# main-unit-psu.net
KiCad netlist of a schematic drawn in EAGLE
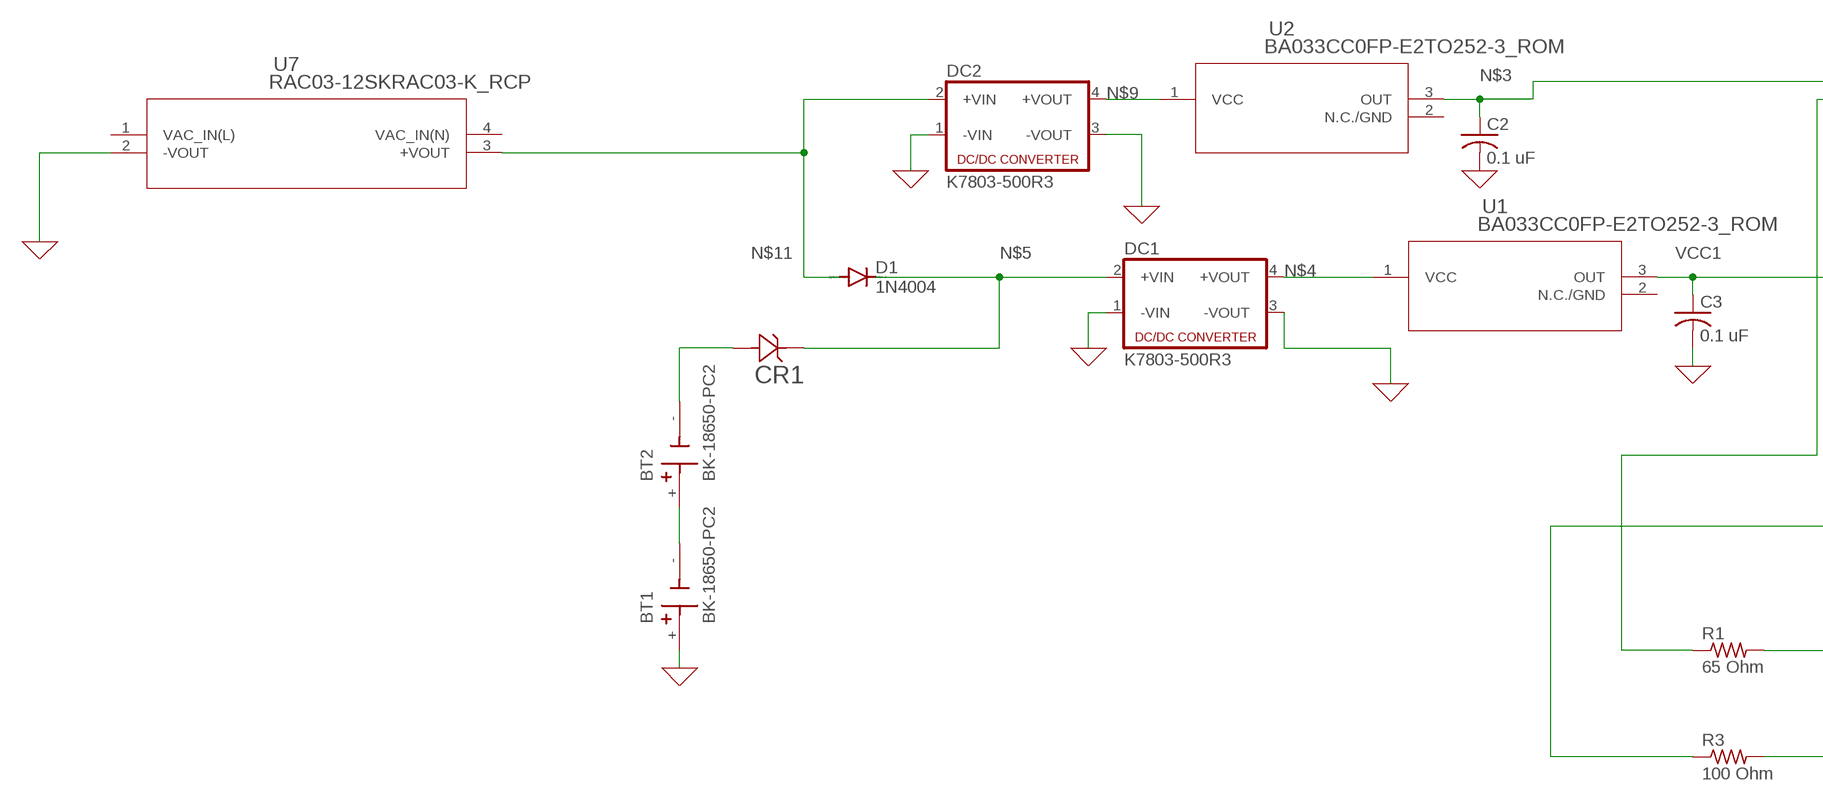
[diagram p0: schematic, sheet 1, part 1 of 2]
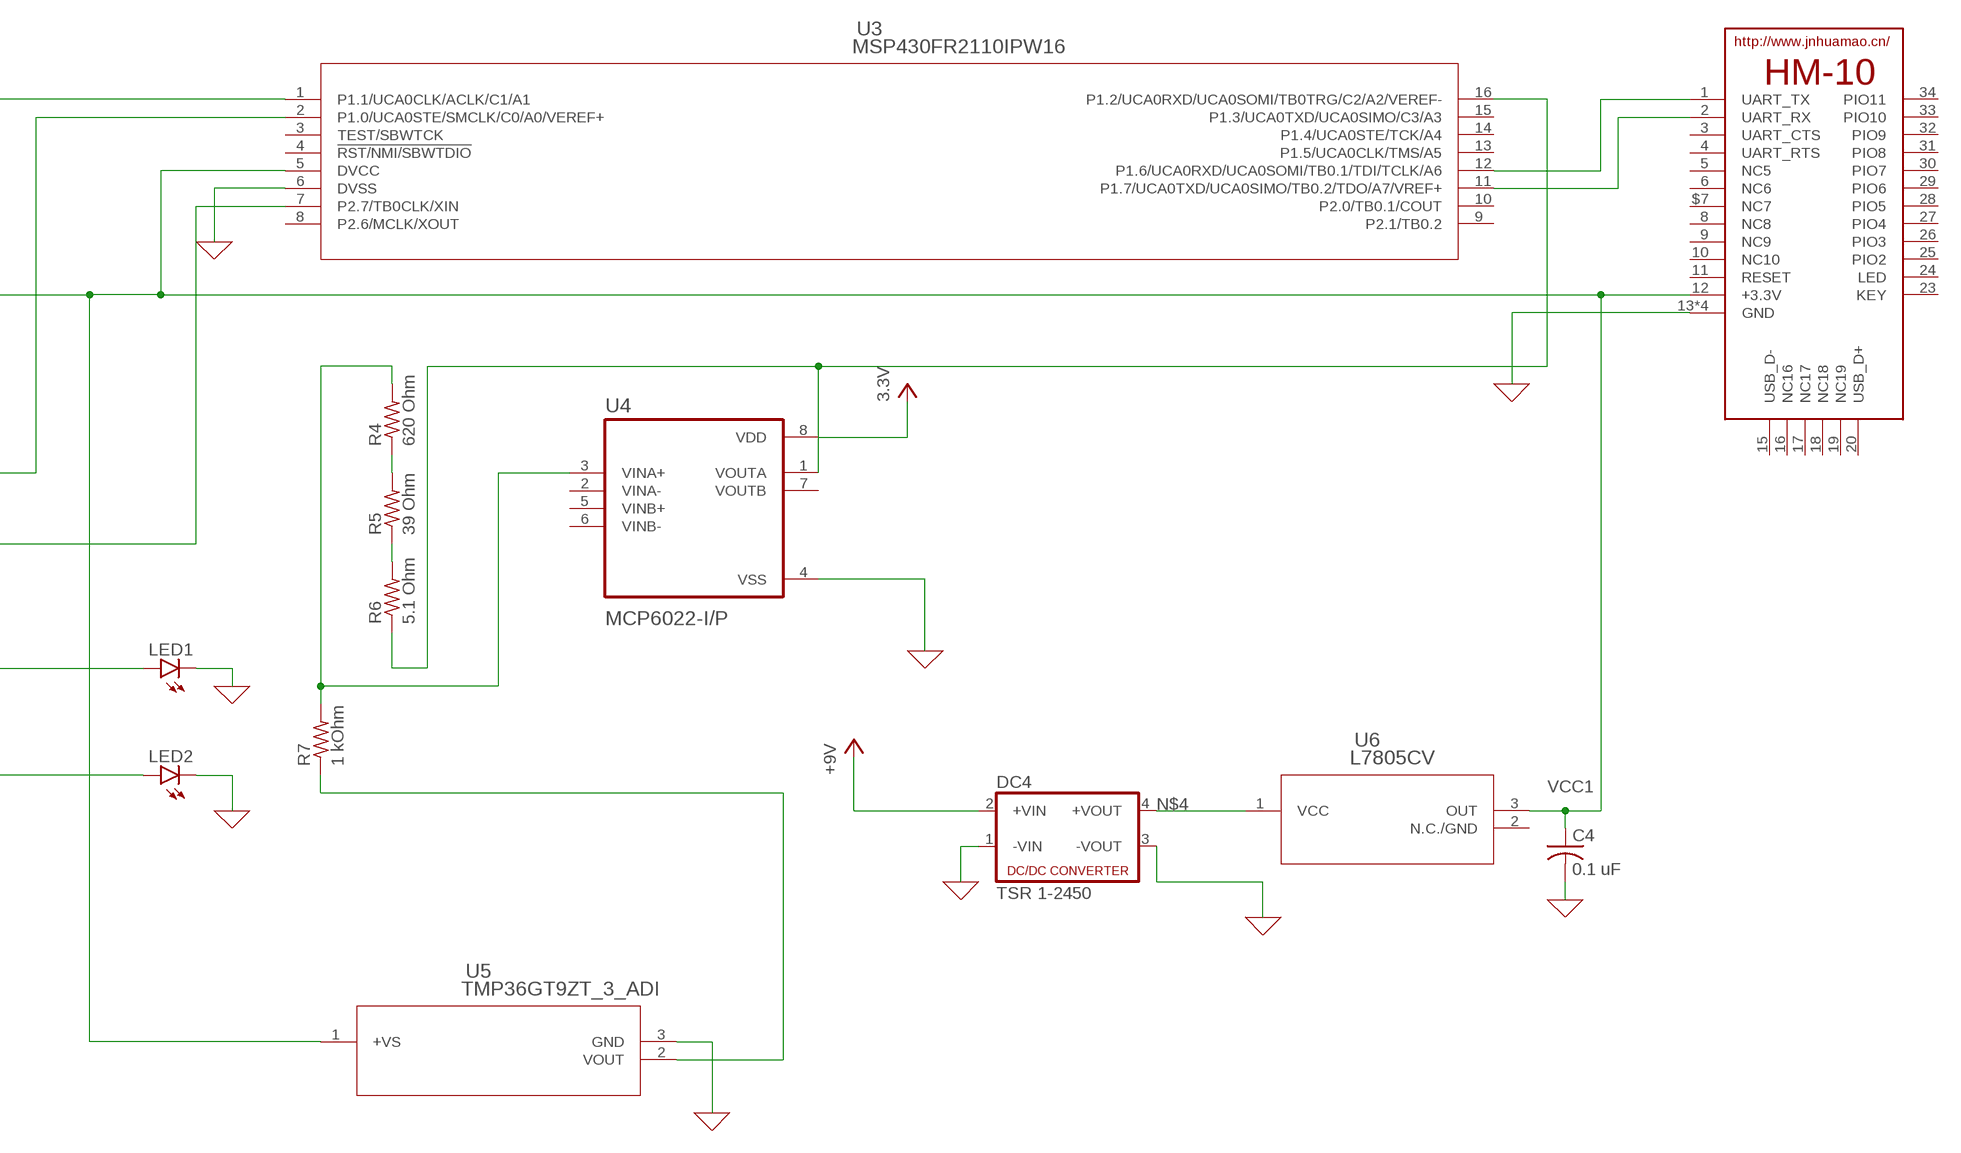
[diagram p1: schematic, sheet 1, part 2 of 2]

(export (version "E")
  (design (tool "Eeschema 10.0.6"))
  (components
    (comp (ref "BT1")
      (value "BK-18650-PC2")
      (footprint "eagle-import:BAT_BK-18650-PC2")
      (fields (field (name "MF") "MPD (Memory Protection Devices)"))
      (libsource (lib "eagle-import") (part "BK-18650-PC2"))
    )
    (comp (ref "BT2")
      (value "BK-18650-PC2")
      (footprint "eagle-import:BAT_BK-18650-PC2")
      (fields (field (name "MF") "MPD (Memory Protection Devices)"))
      (libsource (lib "eagle-import") (part "BK-18650-PC2"))
    )
    (comp (ref "C2")
      (value "0.1 uF")
      (footprint "eagle-import:C050-024X044")
      (libsource (lib "eagle-import") (part "C-US050-024X044"))
    )
    (comp (ref "C3")
      (value "0.1 uF")
      (footprint "eagle-import:C050-024X044")
      (libsource (lib "eagle-import") (part "C-US050-024X044"))
    )
    (comp (ref "C4")
      (value "0.1 uF")
      (footprint "eagle-import:C050-024X044")
      (libsource (lib "eagle-import") (part "C-US050-024X044"))
    )
    (comp (ref "CR1")
      (value "1N5819DO-41_STM")
      (footprint "eagle-import:DO-41_STM")
      (fields
        (field (name "MANUFACTURER_PART_NUMBER") "1N5819")
        (field (name "COPYRIGHT") "Copyright (C) 2023 Ultra Librarian. All rights reserved.")
      )
      (libsource (lib "eagle-import") (part "1N5819DO-41_STM"))
    )
    (comp (ref "D1")
      (value "1N4004")
      (footprint "eagle-import:DO41-10")
      (libsource (lib "eagle-import") (part "1N4004"))
    )
    (comp (ref "DC1")
      (value "K7803-500R3")
      (footprint "eagle-import:NME")
      (fields (field (name "MF") "C & D TECHNOLOGIES, INC") (field (name "MPN") "NME1205D"))
      (libsource (lib "eagle-import") (part "NME"))
    )
    (comp (ref "DC2")
      (value "K7803-500R3")
      (footprint "eagle-import:NME")
      (fields (field (name "MF") "C & D TECHNOLOGIES, INC") (field (name "MPN") "NME1205D"))
      (libsource (lib "eagle-import") (part "NME"))
    )
    (comp (ref "DC4")
      (value "TSR 1-2450")
      (footprint "eagle-import:NME")
      (fields (field (name "MF") "C & D TECHNOLOGIES, INC") (field (name "MPN") "NME1205D"))
      (libsource (lib "eagle-import") (part "NME"))
    )
    (comp (ref "E1")
      (value "HM-10-BOARD")
      (footprint "eagle-import:26.9X13X2.2_BOARD")
      (fields (field (name "MF") "Jinan Huamao Technology") (field (name "MP") "HM-10"))
      (libsource (lib "eagle-import") (part "HM-10-BOARD"))
    )
    (comp (ref "LED1")
      (value "LED5MM")
      (footprint "eagle-import:LED5MM")
      (libsource (lib "eagle-import") (part "LED5MM"))
    )
    (comp (ref "LED2")
      (value "LED5MM")
      (footprint "eagle-import:LED5MM")
      (libsource (lib "eagle-import") (part "LED5MM"))
    )
    (comp (ref "R1")
      (value "65 Ohm")
      (footprint "eagle-import:0204_7")
      (libsource (lib "eagle-import") (part "R-US_0204/7"))
    )
    (comp (ref "R3")
      (value "100 Ohm")
      (footprint "eagle-import:0204_7")
      (libsource (lib "eagle-import") (part "R-US_0204/7"))
    )
    (comp (ref "R4")
      (value "620 Ohm")
      (footprint "eagle-import:0204_7")
      (libsource (lib "eagle-import") (part "R-US_0204/7"))
    )
    (comp (ref "R5")
      (value "39 Ohm")
      (footprint "eagle-import:0204_7")
      (libsource (lib "eagle-import") (part "R-US_0204/7"))
    )
    (comp (ref "R6")
      (value "5.1 Ohm")
      (footprint "eagle-import:0204_7")
      (libsource (lib "eagle-import") (part "R-US_0204/7"))
    )
    (comp (ref "R7")
      (value "1 kOhm")
      (footprint "eagle-import:0204_7")
      (libsource (lib "eagle-import") (part "R-US_0204/7"))
    )
    (comp (ref "U1")
      (value "BA033CC0FP-E2TO252-3_ROM")
      (footprint "eagle-import:TO252-3_ROM")
      (fields
        (field (name "MANUFACTURER_PART_NUMBER") "BA033CC0FP-E2")
        (field (name "COPYRIGHT") "Copyright (C) 2023 Ultra Librarian. All rights reserved.")
      )
      (libsource (lib "eagle-import") (part "BA033CC0FP-E2TO252-3_ROM"))
    )
    (comp (ref "U2")
      (value "BA033CC0FP-E2TO252-3_ROM")
      (footprint "eagle-import:TO252-3_ROM")
      (fields
        (field (name "MANUFACTURER_PART_NUMBER") "BA033CC0FP-E2")
        (field (name "COPYRIGHT") "Copyright (C) 2023 Ultra Librarian. All rights reserved.")
      )
      (libsource (lib "eagle-import") (part "BA033CC0FP-E2TO252-3_ROM"))
    )
    (comp (ref "U3")
      (value "MSP430FR2110IPW16")
      (footprint "eagle-import:PW16_TEX")
      (fields (field (name "COPYRIGHT") "Copyright (C) 2023 Ultra Librarian. All rights reserved."))
      (libsource (lib "eagle-import") (part "MSP430FR2110IPW16"))
    )
    (comp (ref "U4")
      (value "MCP6022-I/P")
      (footprint "eagle-import:DIP787W46P254L927H533Q8")
      (libsource (lib "eagle-import") (part "MCP6022-I/P"))
    )
    (comp (ref "U5")
      (value "TMP36GT9ZT_3_ADI")
      (footprint "eagle-import:T_3_ADI")
      (fields
        (field (name "MANUFACTURER_PART_NUMBER") "TMP36GT9Z")
        (field (name "COPYRIGHT") "Copyright (C) 2023 Ultra Librarian. All rights reserved.")
      )
      (libsource (lib "eagle-import") (part "TMP36GT9ZT_3_ADI"))
    )
    (comp (ref "U6")
      (value "L7805CV")
      (footprint "eagle-import:TO252-3_ROM")
      (fields
        (field (name "MANUFACTURER_PART_NUMBER") "BA033CC0FP-E2")
        (field (name "COPYRIGHT") "Copyright (C) 2023 Ultra Librarian. All rights reserved.")
      )
      (libsource (lib "eagle-import") (part "BA033CC0FP-E2TO252-3_ROM"))
    )
    (comp (ref "U7")
      (value "RAC03-12SKRAC03-K_RCP")
      (footprint "eagle-import:RAC03-K_RCP")
      (fields
        (field (name "MANUFACTURER_PART_NUMBER") "RAC03-12SK")
        (field (name "COPYRIGHT") "Copyright (C) 2023 Ultra Librarian. All rights reserved.")
      )
      (libsource (lib "eagle-import") (part "RAC03-12SKRAC03-K_RCP"))
    )
  )
  (nets
    (net (code "1") (name "+9V") (class "Default")
      (node (ref "DC4") (pin "2") (pinfunction "+VIN_2") (pintype "passive"))
    )
    (net (code "2") (name "/N$3") (class "Default")
      (node (ref "C2") (pin "1") (pinfunction "1_1") (pintype "passive"))
      (node (ref "U2") (pin "3") (pinfunction "OUT_3") (pintype "output"))
      (node (ref "U3") (pin "1") (pinfunction "P1.1/UCA0CLK/ACLK/C1/A1_1") (pintype "bidirectional"))
    )
    (net (code "3") (name "/N$4") (class "Default")
      (node (ref "DC1") (pin "4") (pinfunction "+VOUT_4") (pintype "passive"))
      (node (ref "DC4") (pin "4") (pinfunction "+VOUT_4") (pintype "passive"))
      (node (ref "U1") (pin "1") (pinfunction "VCC_1") (pintype "power_in"))
      (node (ref "U6") (pin "1") (pinfunction "VCC_1") (pintype "power_in"))
    )
    (net (code "4") (name "/N$5") (class "Default")
      (node (ref "CR1") (pin "1") (pinfunction "1_1") (pintype "passive"))
      (node (ref "D1") (pin "C") (pinfunction "C_C") (pintype "passive"))
      (node (ref "DC1") (pin "2") (pinfunction "+VIN_2") (pintype "passive"))
    )
    (net (code "5") (name "/N$9") (class "Default")
      (node (ref "DC2") (pin "4") (pinfunction "+VOUT_4") (pintype "passive"))
      (node (ref "U2") (pin "1") (pinfunction "VCC_1") (pintype "power_in"))
    )
    (net (code "6") (name "/N$11") (class "Default")
      (node (ref "D1") (pin "A") (pinfunction "A_A") (pintype "passive"))
      (node (ref "DC2") (pin "2") (pinfunction "+VIN_2") (pintype "passive"))
      (node (ref "U7") (pin "3") (pinfunction "+VOUT_3") (pintype "output"))
    )
    (net (code "7") (name "/VAC_IN(L)") (class "Default")
      (node (ref "U7") (pin "1") (pinfunction "VAC_IN(L)_1") (pintype "power_in"))
    )
    (net (code "8") (name "/VAC_IN(N)") (class "Default")
      (node (ref "U7") (pin "4") (pinfunction "VAC_IN(N)_4") (pintype "power_in"))
    )
    (net (code "9") (name "/VCC1") (class "Default")
      (node (ref "C3") (pin "1") (pinfunction "1_1") (pintype "passive"))
      (node (ref "C4") (pin "1") (pinfunction "1_1") (pintype "passive"))
      (node (ref "E1") (pin "12") (pinfunction "+3.3V_12") (pintype "bidirectional"))
      (node (ref "U1") (pin "3") (pinfunction "OUT_3") (pintype "output"))
      (node (ref "U3") (pin "5") (pinfunction "DVCC_5") (pintype "power_in"))
      (node (ref "U5") (pin "1") (pinfunction "+VS_1") (pintype "power_in"))
      (node (ref "U6") (pin "3") (pinfunction "OUT_3") (pintype "output"))
    )
    (net (code "10") (name "3.3V") (class "Default")
      (node (ref "U4") (pin "8") (pinfunction "VDD_8") (pintype "power_in"))
    )
    (net (code "11") (name "GND") (class "Default")
      (node (ref "BT1") (pin "+") (pinfunction "+_+") (pintype "passive"))
      (node (ref "C2") (pin "2") (pinfunction "2_2") (pintype "passive"))
      (node (ref "C3") (pin "2") (pinfunction "2_2") (pintype "passive"))
      (node (ref "C4") (pin "2") (pinfunction "2_2") (pintype "passive"))
      (node (ref "DC1") (pin "1") (pinfunction "-VIN_1") (pintype "passive"))
      (node (ref "DC1") (pin "3") (pinfunction "-VOUT_3") (pintype "passive"))
      (node (ref "DC2") (pin "1") (pinfunction "-VIN_1") (pintype "passive"))
      (node (ref "DC2") (pin "3") (pinfunction "-VOUT_3") (pintype "passive"))
      (node (ref "DC4") (pin "1") (pinfunction "-VIN_1") (pintype "passive"))
      (node (ref "DC4") (pin "3") (pinfunction "-VOUT_3") (pintype "passive"))
      (node (ref "E1") (pin "13") (pinfunction "GND_13") (pintype "bidirectional"))
      (node (ref "E1") (pin "14") (pinfunction "GND_14") (pintype "bidirectional"))
      (node (ref "E1") (pin "21") (pinfunction "GND_21") (pintype "bidirectional"))
      (node (ref "E1") (pin "22") (pinfunction "GND_22") (pintype "bidirectional"))
      (node (ref "LED1") (pin "K") (pinfunction "C_K") (pintype "passive"))
      (node (ref "LED2") (pin "K") (pinfunction "C_K") (pintype "passive"))
      (node (ref "U3") (pin "6") (pinfunction "DVSS_6") (pintype "passive"))
      (node (ref "U4") (pin "4") (pinfunction "VSS_4") (pintype "power_in"))
      (node (ref "U5") (pin "3") (pinfunction "GND_3") (pintype "passive"))
      (node (ref "U7") (pin "2") (pinfunction "-VOUT_2") (pintype "output"))
    )
    (net (code "12") (name "Net-(BT1-Pad-)") (class "Default")
      (node (ref "BT1") (pin "-") (pinfunction "-_-") (pintype "passive"))
      (node (ref "BT2") (pin "+") (pinfunction "+_+") (pintype "passive"))
    )
    (net (code "13") (name "Net-(BT2-Pad-)") (class "Default")
      (node (ref "BT2") (pin "-") (pinfunction "-_-") (pintype "passive"))
      (node (ref "CR1") (pin "2") (pinfunction "2_2") (pintype "passive"))
    )
    (net (code "14") (name "Net-(E1-UART_RX)") (class "Default")
      (node (ref "E1") (pin "2") (pinfunction "UART_RX_2") (pintype "bidirectional"))
      (node (ref "U3") (pin "11") (pinfunction "P1.7/UCA0TXD/UCA0SIMO/TB0.2/TDO/A7/VREF+_11") (pintype "bidirectional"))
    )
    (net (code "15") (name "Net-(E1-UART_TX)") (class "Default")
      (node (ref "E1") (pin "1") (pinfunction "UART_TX_1") (pintype "bidirectional"))
      (node (ref "U3") (pin "12") (pinfunction "P1.6/UCA0RXD/UCA0SOMI/TB0.1/TDI/TCLK/A6_12") (pintype "bidirectional"))
    )
    (net (code "16") (name "Net-(LED1-PadA)") (class "Default")
      (node (ref "LED1") (pin "A") (pinfunction "A_A") (pintype "passive"))
      (node (ref "R1") (pin "2") (pinfunction "2_2") (pintype "passive"))
    )
    (net (code "17") (name "Net-(LED2-PadA)") (class "Default")
      (node (ref "LED2") (pin "A") (pinfunction "A_A") (pintype "passive"))
      (node (ref "R3") (pin "2") (pinfunction "2_2") (pintype "passive"))
    )
    (net (code "18") (name "Net-(R4-Pad1)") (class "Default")
      (node (ref "R4") (pin "1") (pinfunction "1_1") (pintype "passive"))
      (node (ref "R5") (pin "2") (pinfunction "2_2") (pintype "passive"))
    )
    (net (code "19") (name "Net-(R5-Pad1)") (class "Default")
      (node (ref "R5") (pin "1") (pinfunction "1_1") (pintype "passive"))
      (node (ref "R6") (pin "2") (pinfunction "2_2") (pintype "passive"))
    )
    (net (code "20") (name "Net-(U3-P1.0{slash}UCA0STE{slash}SMCLK{slash}C0{slash}A0{slash}VEREF+)") (class "Default")
      (node (ref "R1") (pin "1") (pinfunction "1_1") (pintype "passive"))
      (node (ref "U3") (pin "2") (pinfunction "P1.0/UCA0STE/SMCLK/C0/A0/VEREF+_2") (pintype "bidirectional"))
    )
    (net (code "21") (name "Net-(U3-P1.2{slash}UCA0RXD{slash}UCA0SOMI{slash}TB0TRG{slash}C2{slash}A2{slash}VEREF-)") (class "Default")
      (node (ref "R6") (pin "1") (pinfunction "1_1") (pintype "passive"))
      (node (ref "U3") (pin "16") (pinfunction "P1.2/UCA0RXD/UCA0SOMI/TB0TRG/C2/A2/VEREF-_16") (pintype "bidirectional"))
      (node (ref "U4") (pin "1") (pinfunction "VOUTA_1") (pintype "output"))
    )
    (net (code "22") (name "Net-(U3-P2.7{slash}TB0CLK{slash}XIN)") (class "Default")
      (node (ref "R3") (pin "1") (pinfunction "1_1") (pintype "passive"))
      (node (ref "U3") (pin "7") (pinfunction "P2.7/TB0CLK/XIN_7") (pintype "bidirectional"))
    )
    (net (code "23") (name "Net-(U4-VINA+)") (class "Default")
      (node (ref "R4") (pin "2") (pinfunction "2_2") (pintype "passive"))
      (node (ref "R7") (pin "2") (pinfunction "2_2") (pintype "passive"))
      (node (ref "U4") (pin "3") (pinfunction "VINA+_3") (pintype "input"))
    )
    (net (code "24") (name "Net-(U5-VOUT)") (class "Default")
      (node (ref "R7") (pin "1") (pinfunction "1_1") (pintype "passive"))
      (node (ref "U5") (pin "2") (pinfunction "VOUT_2") (pintype "passive"))
    )
    (net (code "25") (name "unconnected-(E1-KEY-Pad23)") (class "Default")
      (node (ref "E1") (pin "23") (pinfunction "KEY_23") (pintype "bidirectional"))
    )
    (net (code "26") (name "unconnected-(E1-LED-Pad24)") (class "Default")
      (node (ref "E1") (pin "24") (pinfunction "LED_24") (pintype "bidirectional"))
    )
    (net (code "27") (name "unconnected-(E1-NC5-Pad5)") (class "Default")
      (node (ref "E1") (pin "5") (pinfunction "NC5_5") (pintype "bidirectional"))
    )
    (net (code "28") (name "unconnected-(E1-NC6-Pad6)") (class "Default")
      (node (ref "E1") (pin "6") (pinfunction "NC6_6") (pintype "bidirectional"))
    )
    (net (code "29") (name "unconnected-(E1-NC7-Pad$7)") (class "Default")
      (node (ref "E1") (pin "$7") (pinfunction "NC7_$7") (pintype "bidirectional"))
    )
    (net (code "30") (name "unconnected-(E1-NC8-Pad8)") (class "Default")
      (node (ref "E1") (pin "8") (pinfunction "NC8_8") (pintype "bidirectional"))
    )
    (net (code "31") (name "unconnected-(E1-NC9-Pad9)") (class "Default")
      (node (ref "E1") (pin "9") (pinfunction "NC9_9") (pintype "bidirectional"))
    )
    (net (code "32") (name "unconnected-(E1-NC10-Pad10)") (class "Default")
      (node (ref "E1") (pin "10") (pinfunction "NC10_10") (pintype "bidirectional"))
    )
    (net (code "33") (name "unconnected-(E1-NC16-Pad16)") (class "Default")
      (node (ref "E1") (pin "16") (pinfunction "NC16_16") (pintype "bidirectional"))
    )
    (net (code "34") (name "unconnected-(E1-NC17-Pad17)") (class "Default")
      (node (ref "E1") (pin "17") (pinfunction "NC17_17") (pintype "bidirectional"))
    )
    (net (code "35") (name "unconnected-(E1-NC18-Pad18)") (class "Default")
      (node (ref "E1") (pin "18") (pinfunction "NC18_18") (pintype "bidirectional"))
    )
    (net (code "36") (name "unconnected-(E1-NC19-Pad19)") (class "Default")
      (node (ref "E1") (pin "19") (pinfunction "NC19_19") (pintype "bidirectional"))
    )
    (net (code "37") (name "unconnected-(E1-PIO2-Pad25)") (class "Default")
      (node (ref "E1") (pin "25") (pinfunction "PIO2_25") (pintype "bidirectional"))
    )
    (net (code "38") (name "unconnected-(E1-PIO3-Pad26)") (class "Default")
      (node (ref "E1") (pin "26") (pinfunction "PIO3_26") (pintype "bidirectional"))
    )
    (net (code "39") (name "unconnected-(E1-PIO4-Pad27)") (class "Default")
      (node (ref "E1") (pin "27") (pinfunction "PIO4_27") (pintype "bidirectional"))
    )
    (net (code "40") (name "unconnected-(E1-PIO5-Pad28)") (class "Default")
      (node (ref "E1") (pin "28") (pinfunction "PIO5_28") (pintype "bidirectional"))
    )
    (net (code "41") (name "unconnected-(E1-PIO6-Pad29)") (class "Default")
      (node (ref "E1") (pin "29") (pinfunction "PIO6_29") (pintype "bidirectional"))
    )
    (net (code "42") (name "unconnected-(E1-PIO7-Pad30)") (class "Default")
      (node (ref "E1") (pin "30") (pinfunction "PIO7_30") (pintype "bidirectional"))
    )
    (net (code "43") (name "unconnected-(E1-PIO8-Pad31)") (class "Default")
      (node (ref "E1") (pin "31") (pinfunction "PIO8_31") (pintype "bidirectional"))
    )
    (net (code "44") (name "unconnected-(E1-PIO9-Pad32)") (class "Default")
      (node (ref "E1") (pin "32") (pinfunction "PIO9_32") (pintype "bidirectional"))
    )
    (net (code "45") (name "unconnected-(E1-PIO10-Pad33)") (class "Default")
      (node (ref "E1") (pin "33") (pinfunction "PIO10_33") (pintype "bidirectional"))
    )
    (net (code "46") (name "unconnected-(E1-PIO11-Pad34)") (class "Default")
      (node (ref "E1") (pin "34") (pinfunction "PIO11_34") (pintype "bidirectional"))
    )
    (net (code "47") (name "unconnected-(E1-RESET-Pad11)") (class "Default")
      (node (ref "E1") (pin "11") (pinfunction "RESET_11") (pintype "bidirectional"))
    )
    (net (code "48") (name "unconnected-(E1-UART_CTS-Pad3)") (class "Default")
      (node (ref "E1") (pin "3") (pinfunction "UART_CTS_3") (pintype "bidirectional"))
    )
    (net (code "49") (name "unconnected-(E1-UART_RTS-Pad4)") (class "Default")
      (node (ref "E1") (pin "4") (pinfunction "UART_RTS_4") (pintype "bidirectional"))
    )
    (net (code "50") (name "unconnected-(E1-USB_D+-Pad20)") (class "Default")
      (node (ref "E1") (pin "20") (pinfunction "USB_D+_20") (pintype "bidirectional"))
    )
    (net (code "51") (name "unconnected-(E1-USB_D--Pad15)") (class "Default")
      (node (ref "E1") (pin "15") (pinfunction "USB_D-_15") (pintype "bidirectional"))
    )
    (net (code "52") (name "unconnected-(U1-N.C.{slash}GND-Pad2)") (class "Default")
      (node (ref "U1") (pin "2") (pinfunction "N.C./GND_2") (pintype "no_connect"))
    )
    (net (code "53") (name "unconnected-(U2-N.C.{slash}GND-Pad2)") (class "Default")
      (node (ref "U2") (pin "2") (pinfunction "N.C./GND_2") (pintype "no_connect"))
    )
    (net (code "54") (name "unconnected-(U3-P1.3{slash}UCA0TXD{slash}UCA0SIMO{slash}C3{slash}A3-Pad15)") (class "Default")
      (node (ref "U3") (pin "15") (pinfunction "P1.3/UCA0TXD/UCA0SIMO/C3/A3_15") (pintype "bidirectional"))
    )
    (net (code "55") (name "unconnected-(U3-P1.4{slash}UCA0STE{slash}TCK{slash}A4-Pad14)") (class "Default")
      (node (ref "U3") (pin "14") (pinfunction "P1.4/UCA0STE/TCK/A4_14") (pintype "bidirectional"))
    )
    (net (code "56") (name "unconnected-(U3-P1.5{slash}UCA0CLK{slash}TMS{slash}A5-Pad13)") (class "Default")
      (node (ref "U3") (pin "13") (pinfunction "P1.5/UCA0CLK/TMS/A5_13") (pintype "bidirectional"))
    )
    (net (code "57") (name "unconnected-(U3-P2.0{slash}TB0.1{slash}COUT-Pad10)") (class "Default")
      (node (ref "U3") (pin "10") (pinfunction "P2.0/TB0.1/COUT_10") (pintype "bidirectional"))
    )
    (net (code "58") (name "unconnected-(U3-P2.1{slash}TB0.2-Pad9)") (class "Default")
      (node (ref "U3") (pin "9") (pinfunction "P2.1/TB0.2_9") (pintype "bidirectional"))
    )
    (net (code "59") (name "unconnected-(U3-P2.6{slash}MCLK{slash}XOUT-Pad8)") (class "Default")
      (node (ref "U3") (pin "8") (pinfunction "P2.6/MCLK/XOUT_8") (pintype "bidirectional"))
    )
    (net (code "60") (name "unconnected-(U3-TEST{slash}SBWTCK-Pad3)") (class "Default")
      (node (ref "U3") (pin "3") (pinfunction "TEST/SBWTCK_3") (pintype "input"))
    )
    (net (code "61") (name "unconnected-(U3-~{RST{slash}NMI{slash}SBWTDIO}-Pad4)") (class "Default")
      (node (ref "U3") (pin "4") (pinfunction "~{RST/NMI/SBWTDIO}_4") (pintype "bidirectional"))
    )
    (net (code "62") (name "unconnected-(U4-VINA--Pad2)") (class "Default")
      (node (ref "U4") (pin "2") (pinfunction "VINA-_2") (pintype "input"))
    )
    (net (code "63") (name "unconnected-(U4-VINB+-Pad5)") (class "Default")
      (node (ref "U4") (pin "5") (pinfunction "VINB+_5") (pintype "input"))
    )
    (net (code "64") (name "unconnected-(U4-VINB--Pad6)") (class "Default")
      (node (ref "U4") (pin "6") (pinfunction "VINB-_6") (pintype "input"))
    )
    (net (code "65") (name "unconnected-(U4-VOUTB-Pad7)") (class "Default")
      (node (ref "U4") (pin "7") (pinfunction "VOUTB_7") (pintype "output"))
    )
    (net (code "66") (name "unconnected-(U6-N.C.{slash}GND-Pad2)") (class "Default")
      (node (ref "U6") (pin "2") (pinfunction "N.C./GND_2") (pintype "no_connect"))
    )
  )
)
